# tinypico_sensor_board.net
KiCad netlist of a schematic drawn in EAGLE
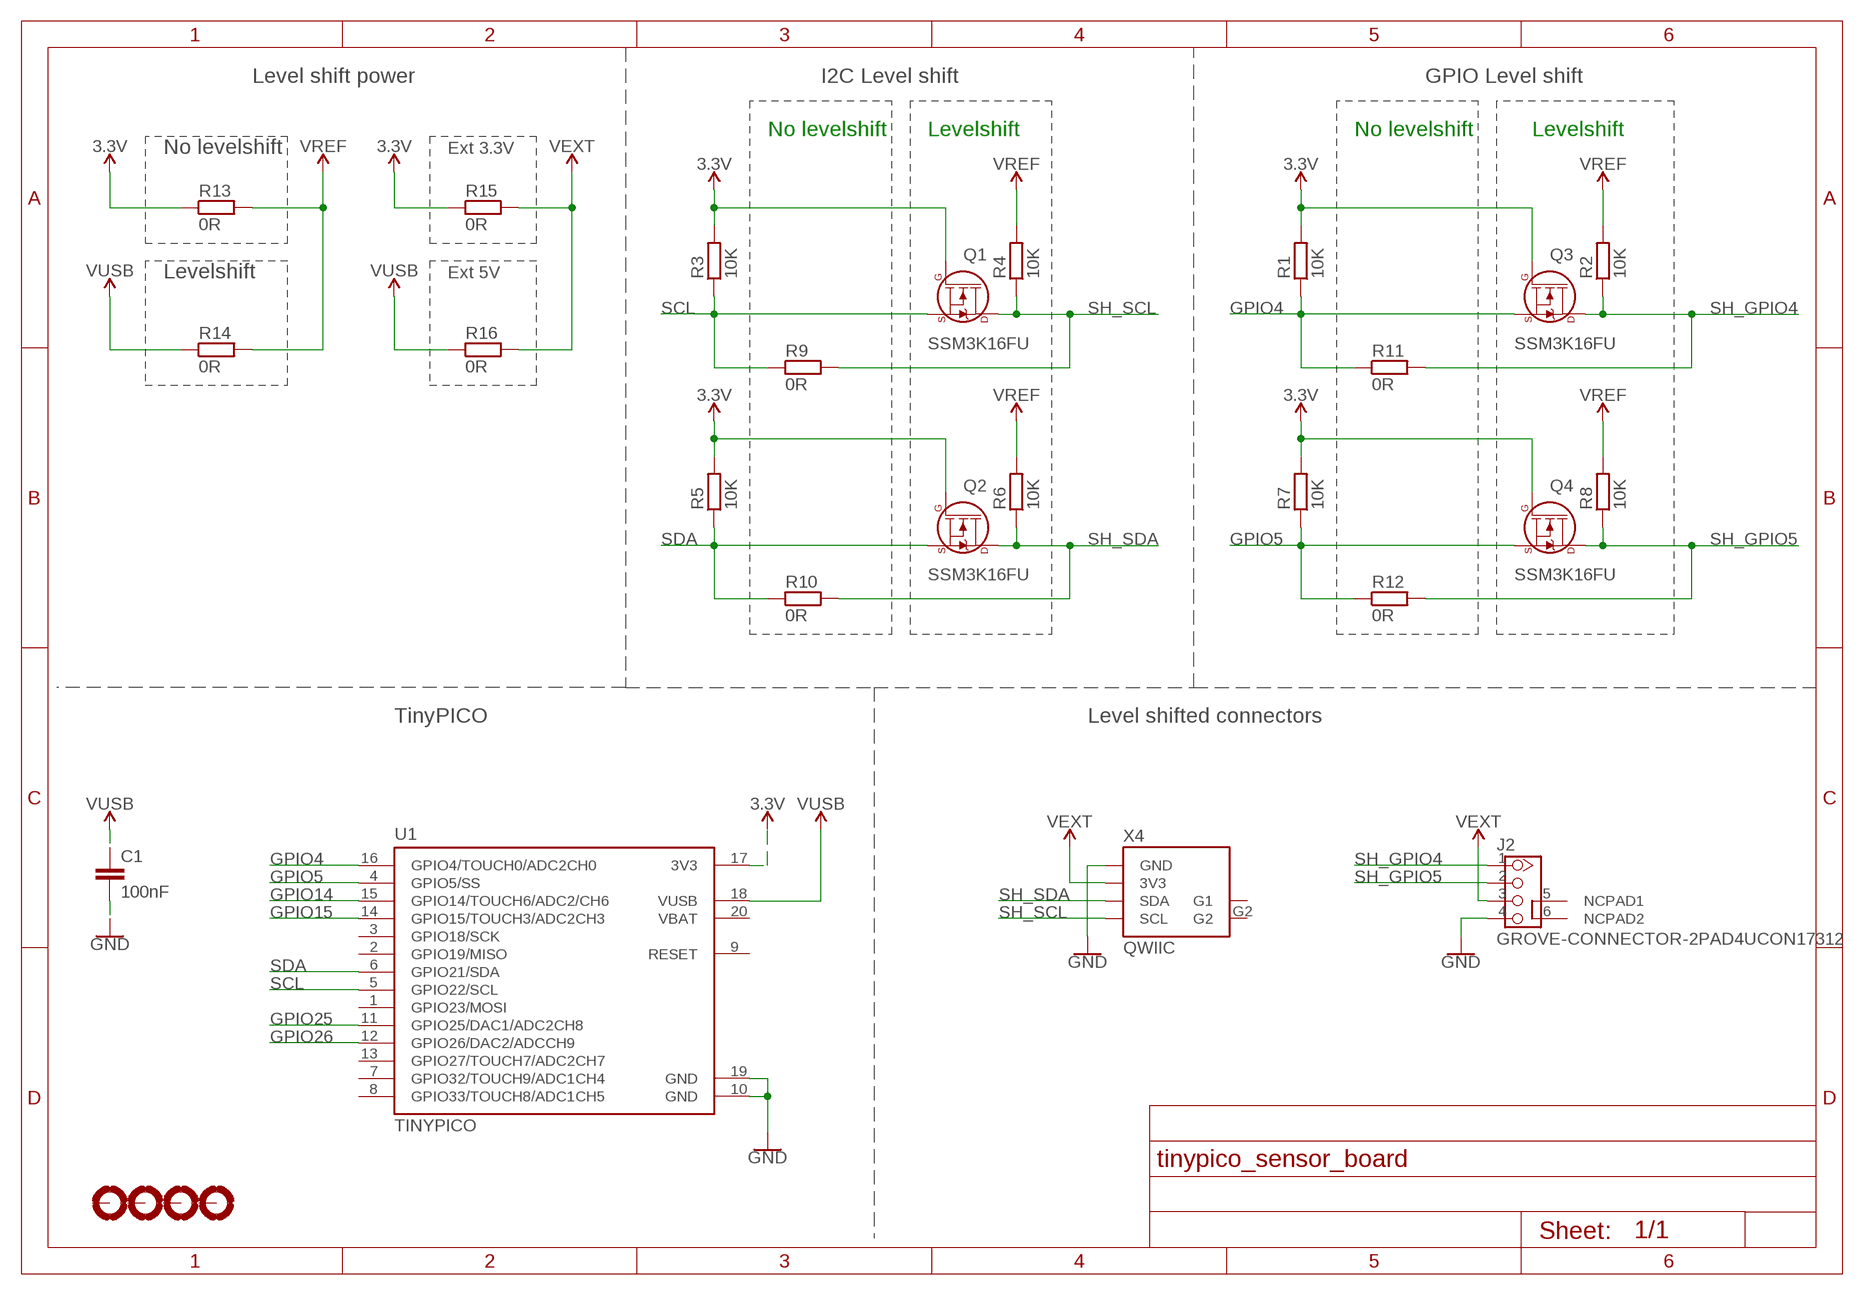
[diagram p0: schematic, sheet 1]

(export (version "E")
  (design (tool "Eeschema 10.0.6"))
  (components
    (comp (ref "C1")
      (value "100nF")
      (footprint "eagle-import:C0603")
      (libsource (lib "eagle-import") (part "CAPC0603"))
    )
    (comp (ref "H1")
      (value "MOUNTHOLE-PAD3.2")
      (footprint "eagle-import:3.2-PAD")
      (libsource (lib "eagle-import") (part "MOUNTHOLE-PAD3.2"))
    )
    (comp (ref "H2")
      (value "MOUNTHOLE-PAD3.2")
      (footprint "eagle-import:3.2-PAD")
      (libsource (lib "eagle-import") (part "MOUNTHOLE-PAD3.2"))
    )
    (comp (ref "H3")
      (value "MOUNTHOLE-PAD3.2")
      (footprint "eagle-import:3.2-PAD")
      (libsource (lib "eagle-import") (part "MOUNTHOLE-PAD3.2"))
    )
    (comp (ref "H4")
      (value "MOUNTHOLE-PAD3.2")
      (footprint "eagle-import:3.2-PAD")
      (libsource (lib "eagle-import") (part "MOUNTHOLE-PAD3.2"))
    )
    (comp (ref "J2")
      (value "GROVE-CONNECTOR-2PAD4UCON17312")
      (footprint "eagle-import:4UCON17312")
      (libsource (lib "eagle-import") (part "GROVE-CONNECTOR-2PAD4UCON17312"))
    )
    (comp (ref "Q1")
      (value "SSM3K16FU")
      (footprint "eagle-import:SOT323")
      (libsource (lib "eagle-import") (part "MOSFET-NCHSOT323"))
    )
    (comp (ref "Q2")
      (value "SSM3K16FU")
      (footprint "eagle-import:SOT323")
      (libsource (lib "eagle-import") (part "MOSFET-NCHSOT323"))
    )
    (comp (ref "Q3")
      (value "SSM3K16FU")
      (footprint "eagle-import:SOT323")
      (libsource (lib "eagle-import") (part "MOSFET-NCHSOT323"))
    )
    (comp (ref "Q4")
      (value "SSM3K16FU")
      (footprint "eagle-import:SOT323")
      (libsource (lib "eagle-import") (part "MOSFET-NCHSOT323"))
    )
    (comp (ref "R1")
      (value "10K")
      (footprint "eagle-import:R0603")
      (libsource (lib "eagle-import") (part "RESISTOR0603"))
    )
    (comp (ref "R2")
      (value "10K")
      (footprint "eagle-import:R0603")
      (libsource (lib "eagle-import") (part "RESISTOR0603"))
    )
    (comp (ref "R3")
      (value "10K")
      (footprint "eagle-import:R0603")
      (libsource (lib "eagle-import") (part "RESISTOR0603"))
    )
    (comp (ref "R4")
      (value "10K")
      (footprint "eagle-import:R0603")
      (libsource (lib "eagle-import") (part "RESISTOR0603"))
    )
    (comp (ref "R5")
      (value "10K")
      (footprint "eagle-import:R0603")
      (libsource (lib "eagle-import") (part "RESISTOR0603"))
    )
    (comp (ref "R6")
      (value "10K")
      (footprint "eagle-import:R0603")
      (libsource (lib "eagle-import") (part "RESISTOR0603"))
    )
    (comp (ref "R7")
      (value "10K")
      (footprint "eagle-import:R0603")
      (libsource (lib "eagle-import") (part "RESISTOR0603"))
    )
    (comp (ref "R8")
      (value "10K")
      (footprint "eagle-import:R0603")
      (libsource (lib "eagle-import") (part "RESISTOR0603"))
    )
    (comp (ref "R9")
      (value "0R")
      (footprint "eagle-import:R0603")
      (libsource (lib "eagle-import") (part "RESISTOR0603"))
    )
    (comp (ref "R10")
      (value "0R")
      (footprint "eagle-import:R0603")
      (libsource (lib "eagle-import") (part "RESISTOR0603"))
    )
    (comp (ref "R11")
      (value "0R")
      (footprint "eagle-import:R0603")
      (libsource (lib "eagle-import") (part "RESISTOR0603"))
    )
    (comp (ref "R12")
      (value "0R")
      (footprint "eagle-import:R0603")
      (libsource (lib "eagle-import") (part "RESISTOR0603"))
    )
    (comp (ref "R13")
      (value "0R")
      (footprint "eagle-import:R1206")
      (libsource (lib "eagle-import") (part "RESISTOR1206"))
    )
    (comp (ref "R14")
      (value "0R")
      (footprint "eagle-import:R1206")
      (libsource (lib "eagle-import") (part "RESISTOR1206"))
    )
    (comp (ref "R15")
      (value "0R")
      (footprint "eagle-import:R1206")
      (libsource (lib "eagle-import") (part "RESISTOR1206"))
    )
    (comp (ref "R16")
      (value "0R")
      (footprint "eagle-import:R1206")
      (libsource (lib "eagle-import") (part "RESISTOR1206"))
    )
    (comp (ref "U1")
      (value "TINYPICO")
      (footprint "eagle-import:TINYPICO")
      (libsource (lib "eagle-import") (part "TINYPICO"))
    )
    (comp (ref "X4")
      (value "QWIIC")
      (footprint "eagle-import:JST-SH-4-SMD-RA")
      (libsource (lib "eagle-import") (part "QWIICRA"))
    )
  )
  (nets
    (net (code "1") (name "/GPIO4") (class "Default")
      (node (ref "Q3") (pin "2") (pinfunction "S_2") (pintype "bidirectional"))
      (node (ref "R1") (pin "1") (pinfunction "1_1") (pintype "passive"))
      (node (ref "R11") (pin "1") (pinfunction "1_1") (pintype "passive"))
      (node (ref "U1") (pin "16") (pinfunction "GPIO4/TOUCH0/ADC2CH0_16") (pintype "bidirectional"))
    )
    (net (code "2") (name "/GPIO5") (class "Default")
      (node (ref "Q4") (pin "2") (pinfunction "S_2") (pintype "bidirectional"))
      (node (ref "R12") (pin "1") (pinfunction "1_1") (pintype "passive"))
      (node (ref "R7") (pin "1") (pinfunction "1_1") (pintype "passive"))
      (node (ref "U1") (pin "4") (pinfunction "GPIO5/SS_4") (pintype "bidirectional"))
    )
    (net (code "3") (name "/GPIO14") (class "Default")
      (node (ref "U1") (pin "15") (pinfunction "GPIO14/TOUCH6/ADC2/CH6_15") (pintype "bidirectional"))
    )
    (net (code "4") (name "/GPIO15") (class "Default")
      (node (ref "U1") (pin "14") (pinfunction "GPIO15/TOUCH3/ADC2CH3_14") (pintype "bidirectional"))
    )
    (net (code "5") (name "/GPIO25") (class "Default")
      (node (ref "U1") (pin "11") (pinfunction "GPIO25/DAC1/ADC2CH8_11") (pintype "bidirectional"))
    )
    (net (code "6") (name "/GPIO26") (class "Default")
      (node (ref "U1") (pin "12") (pinfunction "GPIO26/DAC2/ADCCH9_12") (pintype "bidirectional"))
    )
    (net (code "7") (name "/SCL") (class "Default")
      (node (ref "Q1") (pin "2") (pinfunction "S_2") (pintype "bidirectional"))
      (node (ref "R3") (pin "1") (pinfunction "1_1") (pintype "passive"))
      (node (ref "R9") (pin "1") (pinfunction "1_1") (pintype "passive"))
      (node (ref "U1") (pin "5") (pinfunction "GPIO22/SCL_5") (pintype "bidirectional"))
    )
    (net (code "8") (name "/SDA") (class "Default")
      (node (ref "Q2") (pin "2") (pinfunction "S_2") (pintype "bidirectional"))
      (node (ref "R10") (pin "1") (pinfunction "1_1") (pintype "passive"))
      (node (ref "R5") (pin "1") (pinfunction "1_1") (pintype "passive"))
      (node (ref "U1") (pin "6") (pinfunction "GPIO21/SDA_6") (pintype "bidirectional"))
    )
    (net (code "9") (name "/SH_GPIO4") (class "Default")
      (node (ref "J2") (pin "1") (pinfunction "SCL_1") (pintype "bidirectional"))
      (node (ref "Q3") (pin "3") (pinfunction "D_3") (pintype "bidirectional"))
      (node (ref "R11") (pin "2") (pinfunction "2_2") (pintype "passive"))
      (node (ref "R2") (pin "1") (pinfunction "1_1") (pintype "passive"))
    )
    (net (code "10") (name "/SH_GPIO5") (class "Default")
      (node (ref "J2") (pin "2") (pinfunction "SDA_2") (pintype "bidirectional"))
      (node (ref "Q4") (pin "3") (pinfunction "D_3") (pintype "bidirectional"))
      (node (ref "R12") (pin "2") (pinfunction "2_2") (pintype "passive"))
      (node (ref "R8") (pin "1") (pinfunction "1_1") (pintype "passive"))
    )
    (net (code "11") (name "/SH_SCL") (class "Default")
      (node (ref "Q1") (pin "3") (pinfunction "D_3") (pintype "bidirectional"))
      (node (ref "R4") (pin "1") (pinfunction "1_1") (pintype "passive"))
      (node (ref "R9") (pin "2") (pinfunction "2_2") (pintype "passive"))
      (node (ref "X4") (pin "SCL") (pinfunction "SCL_SCL") (pintype "input"))
    )
    (net (code "12") (name "/SH_SDA") (class "Default")
      (node (ref "Q2") (pin "3") (pinfunction "D_3") (pintype "bidirectional"))
      (node (ref "R10") (pin "2") (pinfunction "2_2") (pintype "passive"))
      (node (ref "R6") (pin "1") (pinfunction "1_1") (pintype "passive"))
      (node (ref "X4") (pin "SDA") (pinfunction "SDA_SDA") (pintype "bidirectional"))
    )
    (net (code "13") (name "3.3V") (class "Default")
      (node (ref "Q1") (pin "1") (pinfunction "G_1") (pintype "bidirectional"))
      (node (ref "Q2") (pin "1") (pinfunction "G_1") (pintype "bidirectional"))
      (node (ref "Q3") (pin "1") (pinfunction "G_1") (pintype "bidirectional"))
      (node (ref "Q4") (pin "1") (pinfunction "G_1") (pintype "bidirectional"))
      (node (ref "R1") (pin "2") (pinfunction "2_2") (pintype "passive"))
      (node (ref "R13") (pin "1") (pinfunction "1_1") (pintype "passive"))
      (node (ref "R15") (pin "1") (pinfunction "1_1") (pintype "passive"))
      (node (ref "R3") (pin "2") (pinfunction "2_2") (pintype "passive"))
      (node (ref "R5") (pin "2") (pinfunction "2_2") (pintype "passive"))
      (node (ref "R7") (pin "2") (pinfunction "2_2") (pintype "passive"))
      (node (ref "U1") (pin "17") (pinfunction "3V3_17") (pintype "bidirectional"))
    )
    (net (code "14") (name "GND") (class "Default")
      (node (ref "C1") (pin "2") (pinfunction "2_2") (pintype "passive"))
      (node (ref "J2") (pin "4") (pinfunction "GND_4") (pintype "bidirectional"))
      (node (ref "U1") (pin "10") (pinfunction "GND_10") (pintype "bidirectional"))
      (node (ref "U1") (pin "19") (pinfunction "GND_19") (pintype "bidirectional"))
      (node (ref "X4") (pin "GND") (pinfunction "GND_GND") (pintype "power_in"))
    )
    (net (code "15") (name "VEXT") (class "Default")
      (node (ref "J2") (pin "3") (pinfunction "VCC_3") (pintype "bidirectional"))
      (node (ref "R15") (pin "2") (pinfunction "2_2") (pintype "passive"))
      (node (ref "R16") (pin "2") (pinfunction "2_2") (pintype "passive"))
      (node (ref "X4") (pin "3V3") (pinfunction "3V3_3V3") (pintype "power_in"))
    )
    (net (code "16") (name "VREF") (class "Default")
      (node (ref "R13") (pin "2") (pinfunction "2_2") (pintype "passive"))
      (node (ref "R14") (pin "2") (pinfunction "2_2") (pintype "passive"))
      (node (ref "R2") (pin "2") (pinfunction "2_2") (pintype "passive"))
      (node (ref "R4") (pin "2") (pinfunction "2_2") (pintype "passive"))
      (node (ref "R6") (pin "2") (pinfunction "2_2") (pintype "passive"))
      (node (ref "R8") (pin "2") (pinfunction "2_2") (pintype "passive"))
    )
    (net (code "17") (name "VUSB") (class "Default")
      (node (ref "C1") (pin "1") (pinfunction "1_1") (pintype "passive"))
      (node (ref "R14") (pin "1") (pinfunction "1_1") (pintype "passive"))
      (node (ref "R16") (pin "1") (pinfunction "1_1") (pintype "passive"))
      (node (ref "U1") (pin "18") (pinfunction "VUSB_18") (pintype "bidirectional"))
    )
    (net (code "18") (name "unconnected-(H1-MOUNT-PadB3,2)") (class "Default")
      (node (ref "H1") (pin "B3,2") (pinfunction "MOUNT_B3,2") (pintype "passive"))
    )
    (net (code "19") (name "unconnected-(H2-MOUNT-PadB3,2)") (class "Default")
      (node (ref "H2") (pin "B3,2") (pinfunction "MOUNT_B3,2") (pintype "passive"))
    )
    (net (code "20") (name "unconnected-(H3-MOUNT-PadB3,2)") (class "Default")
      (node (ref "H3") (pin "B3,2") (pinfunction "MOUNT_B3,2") (pintype "passive"))
    )
    (net (code "21") (name "unconnected-(H4-MOUNT-PadB3,2)") (class "Default")
      (node (ref "H4") (pin "B3,2") (pinfunction "MOUNT_B3,2") (pintype "passive"))
    )
    (net (code "22") (name "unconnected-(J2-NCPAD1-Pad5)") (class "Default")
      (node (ref "J2") (pin "5") (pinfunction "NCPAD1_5") (pintype "bidirectional"))
    )
    (net (code "23") (name "unconnected-(J2-NCPAD2-Pad6)") (class "Default")
      (node (ref "J2") (pin "6") (pinfunction "NCPAD2_6") (pintype "bidirectional"))
    )
    (net (code "24") (name "unconnected-(U1-GPIO18{slash}SCK-Pad3)") (class "Default")
      (node (ref "U1") (pin "3") (pinfunction "GPIO18/SCK_3") (pintype "bidirectional"))
    )
    (net (code "25") (name "unconnected-(U1-GPIO19{slash}MISO-Pad2)") (class "Default")
      (node (ref "U1") (pin "2") (pinfunction "GPIO19/MISO_2") (pintype "bidirectional"))
    )
    (net (code "26") (name "unconnected-(U1-GPIO23{slash}MOSI-Pad1)") (class "Default")
      (node (ref "U1") (pin "1") (pinfunction "GPIO23/MOSI_1") (pintype "bidirectional"))
    )
    (net (code "27") (name "unconnected-(U1-GPIO27{slash}TOUCH7{slash}ADC2CH7-Pad13)") (class "Default")
      (node (ref "U1") (pin "13") (pinfunction "GPIO27/TOUCH7/ADC2CH7_13") (pintype "bidirectional"))
    )
    (net (code "28") (name "unconnected-(U1-GPIO32{slash}TOUCH9{slash}ADC1CH4-Pad7)") (class "Default")
      (node (ref "U1") (pin "7") (pinfunction "GPIO32/TOUCH9/ADC1CH4_7") (pintype "bidirectional"))
    )
    (net (code "29") (name "unconnected-(U1-GPIO33{slash}TOUCH8{slash}ADC1CH5-Pad8)") (class "Default")
      (node (ref "U1") (pin "8") (pinfunction "GPIO33/TOUCH8/ADC1CH5_8") (pintype "bidirectional"))
    )
    (net (code "30") (name "unconnected-(U1-RESET-Pad9)") (class "Default")
      (node (ref "U1") (pin "9") (pinfunction "RESET_9") (pintype "bidirectional"))
    )
    (net (code "31") (name "unconnected-(U1-VBAT-Pad20)") (class "Default")
      (node (ref "U1") (pin "20") (pinfunction "VBAT_20") (pintype "bidirectional"))
    )
    (net (code "32") (name "unconnected-(X4-PadG1)") (class "Default")
      (node (ref "X4") (pin "G1") (pinfunction "G1_G1") (pintype "passive"))
    )
    (net (code "33") (name "unconnected-(X4-PadG2)") (class "Default")
      (node (ref "X4") (pin "G2") (pinfunction "G2_G2") (pintype "passive"))
    )
  )
)
